# Cell.net
KiCad netlist of a schematic drawn in Altium Designer
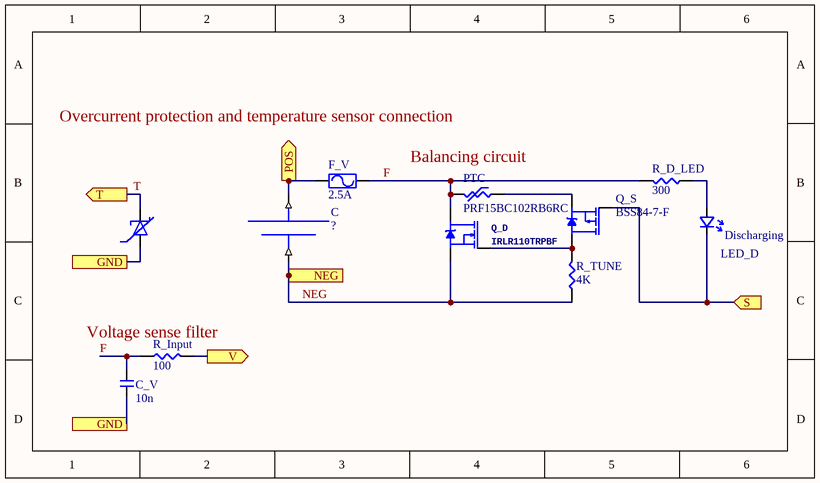
[diagram p0: Cell.SchDoc]

(export (version "E")
  (design (tool "Eeschema 10.0.6"))
  (components
    (comp (ref "C") (value "?") (footprint "Li1x7pVTC6T") (libsource (lib "LTC6811") (part "Li1x7pVTC6T")))
    (comp (ref "C_V")
      (value "10n")
      (footprint "CAP-0603")
      (description "CAP-0603")
      (libsource (lib "altium-import") (part "root_1_CAP-0603_"))
    )
    (comp (ref "F_V") (value "2.5A") (footprint "FUSE1206") (libsource (lib "LTC6811") (part "FUSE-1206")))
    (comp (ref "LED_D")
      (value "Discharging")
      (footprint "LED-0603")
      (description "LED-0603")
      (libsource (lib "altium-import") (part "root_3_LED-0603_"))
    )
    (comp (ref "PTC")
      (value "PRF15BC102RB6RC")
      (footprint "NTC-0603")
      (libsource (lib "ife19_Elec_Library") (part "NTC-0603"))
    )
    (comp (ref "Q_D")
      (value "IRLR110TRPBF")
      (footprint "TO252")
      (libsource (lib "LTC6811") (part "NMOS-TO252"))
    )
    (comp (ref "Q_S")
      (value "BSS84-7-F")
      (footprint "SOT23")
      (libsource (lib "ife19_Elec_Library") (part "PMOS-SOT23"))
    )
    (comp (ref "R_D_LED")
      (value "300")
      (footprint "RES-0603")
      (libsource (lib "altium-import") (part "root_2_RES-0603_"))
    )
    (comp (ref "R_Input")
      (value "100")
      (footprint "RES-0603")
      (libsource (lib "altium-import") (part "root_0_RES-0603_"))
    )
    (comp (ref "R_TUNE")
      (value "4K")
      (footprint "RES-0603")
      (libsource (lib "ife19_Elec_Library") (part "RES-0603"))
    )
  )
  (nets
    (net (code "1") (name "/F") (class "Default")
      (node (ref "C_V") (pin "2") (pinfunction "2_2") (pintype "passive"))
      (node (ref "F_V") (pin "2") (pinfunction "2_2") (pintype "passive"))
      (node (ref "PTC") (pin "2") (pinfunction "2_2") (pintype "passive"))
      (node (ref "Q_D") (pin "2") (pinfunction "D_2") (pintype "passive"))
      (node (ref "R_D_LED") (pin "2") (pinfunction "2_2") (pintype "passive"))
      (node (ref "R_Input") (pin "1") (pinfunction "1_1") (pintype "passive"))
    )
    (net (code "2") (name "/GND") (class "Default")
      (node (ref "C") (pin "T-") (pinfunction "T-_T-") (pintype "passive"))
      (node (ref "C_V") (pin "1") (pinfunction "1_1") (pintype "passive"))
    )
    (net (code "3") (name "/NEG") (class "Default")
      (node (ref "C") (pin "-") (pinfunction "-_-") (pintype "input"))
      (node (ref "Q_D") (pin "3") (pinfunction "S_3") (pintype "passive"))
      (node (ref "R_TUNE") (pin "1") (pinfunction "1_1") (pintype "passive"))
    )
    (net (code "4") (name "/POS") (class "Default")
      (node (ref "C") (pin "+") (pinfunction "+_+") (pintype "output"))
      (node (ref "F_V") (pin "1") (pinfunction "1_1") (pintype "passive"))
    )
    (net (code "5") (name "/S") (class "Default")
      (node (ref "LED_D") (pin "K") (pinfunction "K_K") (pintype "passive"))
      (node (ref "Q_S") (pin "1") (pinfunction "G_1") (pintype "passive"))
    )
    (net (code "6") (name "/T") (class "Default")
      (node (ref "C") (pin "T+") (pinfunction "T+_T+") (pintype "passive"))
    )
    (net (code "7") (name "/V") (class "Default")
      (node (ref "R_Input") (pin "2") (pinfunction "2_2") (pintype "passive"))
    )
    (net (code "8") (name "Net-(LED_D-PadA)") (class "Default")
      (node (ref "LED_D") (pin "A") (pinfunction "A_A") (pintype "passive"))
      (node (ref "R_D_LED") (pin "1") (pinfunction "1_1") (pintype "passive"))
    )
    (net (code "9") (name "Net-(Q_D-G)") (class "Default")
      (node (ref "Q_D") (pin "1") (pinfunction "G_1") (pintype "passive"))
      (node (ref "Q_S") (pin "3") (pinfunction "D_3") (pintype "passive"))
      (node (ref "R_TUNE") (pin "2") (pinfunction "2_2") (pintype "passive"))
    )
    (net (code "10") (name "Net-(Q_S-S)") (class "Default")
      (node (ref "PTC") (pin "1") (pinfunction "1_1") (pintype "passive"))
      (node (ref "Q_S") (pin "2") (pinfunction "S_2") (pintype "passive"))
    )
  )
)
